# simpleROM.net
KiCad netlist of a schematic drawn in Altium Designer
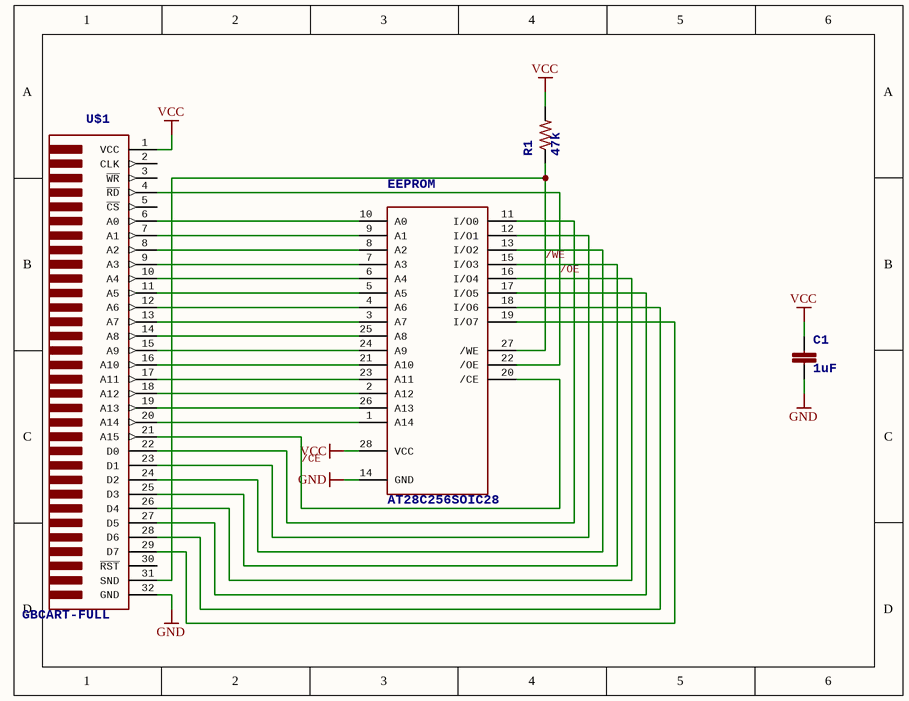
[diagram p0: simpleROM.SchDoc]

(export (version "E")
  (design (tool "Eeschema 10.0.6"))
  (components
    (comp (ref "C1")
      (value "1uF")
      (footprint "SPARKFUN-CAPACITORS_1206")
      (description "<b>Capacitor</b>\nStandard 0603 ceramic capacitor, and 0.1\" leaded capacitor.")
      (fields (field (name ">NAME") "C1") (field (name ">VALUE") "1uF"))
      (libsource (lib "Mega8515_flasher") (part "SPARKFUN-CAPACITORS_CAP1206"))
    )
    (comp (ref "EEPROM")
      (value "AT28C256SOIC28")
      (footprint "SO28")
      (fields (field (name ">NAME") "EEPROM") (field (name ">VALUE") "AT28C256SOIC28"))
      (libsource (lib "gameboy") (part "AT28C256SOIC28"))
    )
    (comp (ref "R1")
      (value "47k")
      (footprint "SPARKFUN-RESISTORS_1206")
      (description "<b>Resistor</b>\nBasic schematic elements and footprints for 0603, 1206, and PTH resistors.")
      (fields (field (name ">NAME") "R1") (field (name ">VALUE") "47k"))
      (libsource (lib "Mega8515_flasher") (part "SPARKFUN-RESISTORS_RESISTOR1206"))
    )
    (comp (ref "U$1")
      (value "GBCART-FULL")
      (footprint "GBCART")
      (fields (field (name ">VALUE") "GBCART-FULL") (field (name ">NAME") "U$1"))
      (libsource (lib "gameboy") (part "GBCART-FULL"))
    )
  )
  (nets
    (net (code "1") (name "/{slash}CE") (class "Default")
      (node (ref "EEPROM") (pin "20") (pinfunction "/CE_20") (pintype "passive"))
      (node (ref "U$1") (pin "21") (pinfunction "A15_21") (pintype "output"))
    )
    (net (code "2") (name "/{slash}OE") (class "Default")
      (node (ref "EEPROM") (pin "22") (pinfunction "/OE_22") (pintype "passive"))
      (node (ref "U$1") (pin "4") (pinfunction "~{RD}_4") (pintype "output"))
    )
    (net (code "3") (name "/{slash}WE") (class "Default")
      (node (ref "EEPROM") (pin "27") (pinfunction "/WE_27") (pintype "passive"))
      (node (ref "R1") (pin "1") (pinfunction "1_1") (pintype "passive"))
      (node (ref "U$1") (pin "31") (pinfunction "SND_31") (pintype "passive"))
    )
    (net (code "4") (name "GND") (class "Default")
      (node (ref "C1") (pin "2") (pinfunction "2_2") (pintype "passive"))
      (node (ref "EEPROM") (pin "14") (pinfunction "GND_14") (pintype "passive"))
      (node (ref "U$1") (pin "32") (pinfunction "GND_32") (pintype "power_in"))
    )
    (net (code "5") (name "Net-(EEPROM-A0)") (class "Default")
      (node (ref "EEPROM") (pin "10") (pinfunction "A0_10") (pintype "passive"))
      (node (ref "U$1") (pin "6") (pinfunction "A0_6") (pintype "output"))
    )
    (net (code "6") (name "Net-(EEPROM-A1)") (class "Default")
      (node (ref "EEPROM") (pin "9") (pinfunction "A1_9") (pintype "passive"))
      (node (ref "U$1") (pin "7") (pinfunction "A1_7") (pintype "output"))
    )
    (net (code "7") (name "Net-(EEPROM-A2)") (class "Default")
      (node (ref "EEPROM") (pin "8") (pinfunction "A2_8") (pintype "passive"))
      (node (ref "U$1") (pin "8") (pinfunction "A2_8") (pintype "output"))
    )
    (net (code "8") (name "Net-(EEPROM-A3)") (class "Default")
      (node (ref "EEPROM") (pin "7") (pinfunction "A3_7") (pintype "passive"))
      (node (ref "U$1") (pin "9") (pinfunction "A3_9") (pintype "output"))
    )
    (net (code "9") (name "Net-(EEPROM-A4)") (class "Default")
      (node (ref "EEPROM") (pin "6") (pinfunction "A4_6") (pintype "passive"))
      (node (ref "U$1") (pin "10") (pinfunction "A4_10") (pintype "output"))
    )
    (net (code "10") (name "Net-(EEPROM-A5)") (class "Default")
      (node (ref "EEPROM") (pin "5") (pinfunction "A5_5") (pintype "passive"))
      (node (ref "U$1") (pin "11") (pinfunction "A5_11") (pintype "output"))
    )
    (net (code "11") (name "Net-(EEPROM-A6)") (class "Default")
      (node (ref "EEPROM") (pin "4") (pinfunction "A6_4") (pintype "passive"))
      (node (ref "U$1") (pin "12") (pinfunction "A6_12") (pintype "output"))
    )
    (net (code "12") (name "Net-(EEPROM-A7)") (class "Default")
      (node (ref "EEPROM") (pin "3") (pinfunction "A7_3") (pintype "passive"))
      (node (ref "U$1") (pin "13") (pinfunction "A7_13") (pintype "output"))
    )
    (net (code "13") (name "Net-(EEPROM-A8)") (class "Default")
      (node (ref "EEPROM") (pin "25") (pinfunction "A8_25") (pintype "passive"))
      (node (ref "U$1") (pin "14") (pinfunction "A8_14") (pintype "output"))
    )
    (net (code "14") (name "Net-(EEPROM-A9)") (class "Default")
      (node (ref "EEPROM") (pin "24") (pinfunction "A9_24") (pintype "passive"))
      (node (ref "U$1") (pin "15") (pinfunction "A9_15") (pintype "output"))
    )
    (net (code "15") (name "Net-(EEPROM-A10)") (class "Default")
      (node (ref "EEPROM") (pin "21") (pinfunction "A10_21") (pintype "passive"))
      (node (ref "U$1") (pin "16") (pinfunction "A10_16") (pintype "output"))
    )
    (net (code "16") (name "Net-(EEPROM-A11)") (class "Default")
      (node (ref "EEPROM") (pin "23") (pinfunction "A11_23") (pintype "passive"))
      (node (ref "U$1") (pin "17") (pinfunction "A11_17") (pintype "output"))
    )
    (net (code "17") (name "Net-(EEPROM-A12)") (class "Default")
      (node (ref "EEPROM") (pin "2") (pinfunction "A12_2") (pintype "passive"))
      (node (ref "U$1") (pin "18") (pinfunction "A12_18") (pintype "output"))
    )
    (net (code "18") (name "Net-(EEPROM-A13)") (class "Default")
      (node (ref "EEPROM") (pin "26") (pinfunction "A13_26") (pintype "passive"))
      (node (ref "U$1") (pin "19") (pinfunction "A13_19") (pintype "output"))
    )
    (net (code "19") (name "Net-(EEPROM-A14)") (class "Default")
      (node (ref "EEPROM") (pin "1") (pinfunction "A14_1") (pintype "passive"))
      (node (ref "U$1") (pin "20") (pinfunction "A14_20") (pintype "output"))
    )
    (net (code "20") (name "Net-(EEPROM-I{slash}O0)") (class "Default")
      (node (ref "EEPROM") (pin "11") (pinfunction "I/O0_11") (pintype "passive"))
      (node (ref "U$1") (pin "22") (pinfunction "D0_22") (pintype "passive"))
    )
    (net (code "21") (name "Net-(EEPROM-I{slash}O1)") (class "Default")
      (node (ref "EEPROM") (pin "12") (pinfunction "I/O1_12") (pintype "passive"))
      (node (ref "U$1") (pin "23") (pinfunction "D1_23") (pintype "passive"))
    )
    (net (code "22") (name "Net-(EEPROM-I{slash}O2)") (class "Default")
      (node (ref "EEPROM") (pin "13") (pinfunction "I/O2_13") (pintype "passive"))
      (node (ref "U$1") (pin "24") (pinfunction "D2_24") (pintype "passive"))
    )
    (net (code "23") (name "Net-(EEPROM-I{slash}O3)") (class "Default")
      (node (ref "EEPROM") (pin "15") (pinfunction "I/O3_15") (pintype "passive"))
      (node (ref "U$1") (pin "25") (pinfunction "D3_25") (pintype "passive"))
    )
    (net (code "24") (name "Net-(EEPROM-I{slash}O4)") (class "Default")
      (node (ref "EEPROM") (pin "16") (pinfunction "I/O4_16") (pintype "passive"))
      (node (ref "U$1") (pin "26") (pinfunction "D4_26") (pintype "passive"))
    )
    (net (code "25") (name "Net-(EEPROM-I{slash}O5)") (class "Default")
      (node (ref "EEPROM") (pin "17") (pinfunction "I/O5_17") (pintype "passive"))
      (node (ref "U$1") (pin "27") (pinfunction "D5_27") (pintype "passive"))
    )
    (net (code "26") (name "Net-(EEPROM-I{slash}O6)") (class "Default")
      (node (ref "EEPROM") (pin "18") (pinfunction "I/O6_18") (pintype "passive"))
      (node (ref "U$1") (pin "28") (pinfunction "D6_28") (pintype "passive"))
    )
    (net (code "27") (name "Net-(EEPROM-I{slash}O7)") (class "Default")
      (node (ref "EEPROM") (pin "19") (pinfunction "I/O7_19") (pintype "passive"))
      (node (ref "U$1") (pin "29") (pinfunction "D7_29") (pintype "passive"))
    )
    (net (code "28") (name "VCC") (class "Default")
      (node (ref "C1") (pin "1") (pinfunction "1_1") (pintype "passive"))
      (node (ref "EEPROM") (pin "28") (pinfunction "VCC_28") (pintype "passive"))
      (node (ref "R1") (pin "2") (pinfunction "2_2") (pintype "passive"))
      (node (ref "U$1") (pin "1") (pinfunction "VCC_1") (pintype "power_in"))
    )
    (net (code "29") (name "unconnected-(U$1-CLK-Pad2)") (class "Default")
      (node (ref "U$1") (pin "2") (pinfunction "CLK_2") (pintype "output"))
    )
    (net (code "30") (name "unconnected-(U$1-~{CS}-Pad5)") (class "Default")
      (node (ref "U$1") (pin "5") (pinfunction "~{CS}_5") (pintype "output"))
    )
    (net (code "31") (name "unconnected-(U$1-~{RST}-Pad30)") (class "Default")
      (node (ref "U$1") (pin "30") (pinfunction "~{RST}_30") (pintype "passive"))
    )
    (net (code "32") (name "unconnected-(U$1-~{WR}-Pad3)") (class "Default")
      (node (ref "U$1") (pin "3") (pinfunction "~{WR}_3") (pintype "output"))
    )
  )
)
